# MOTOR.net
KiCad netlist of a schematic drawn in EAGLE
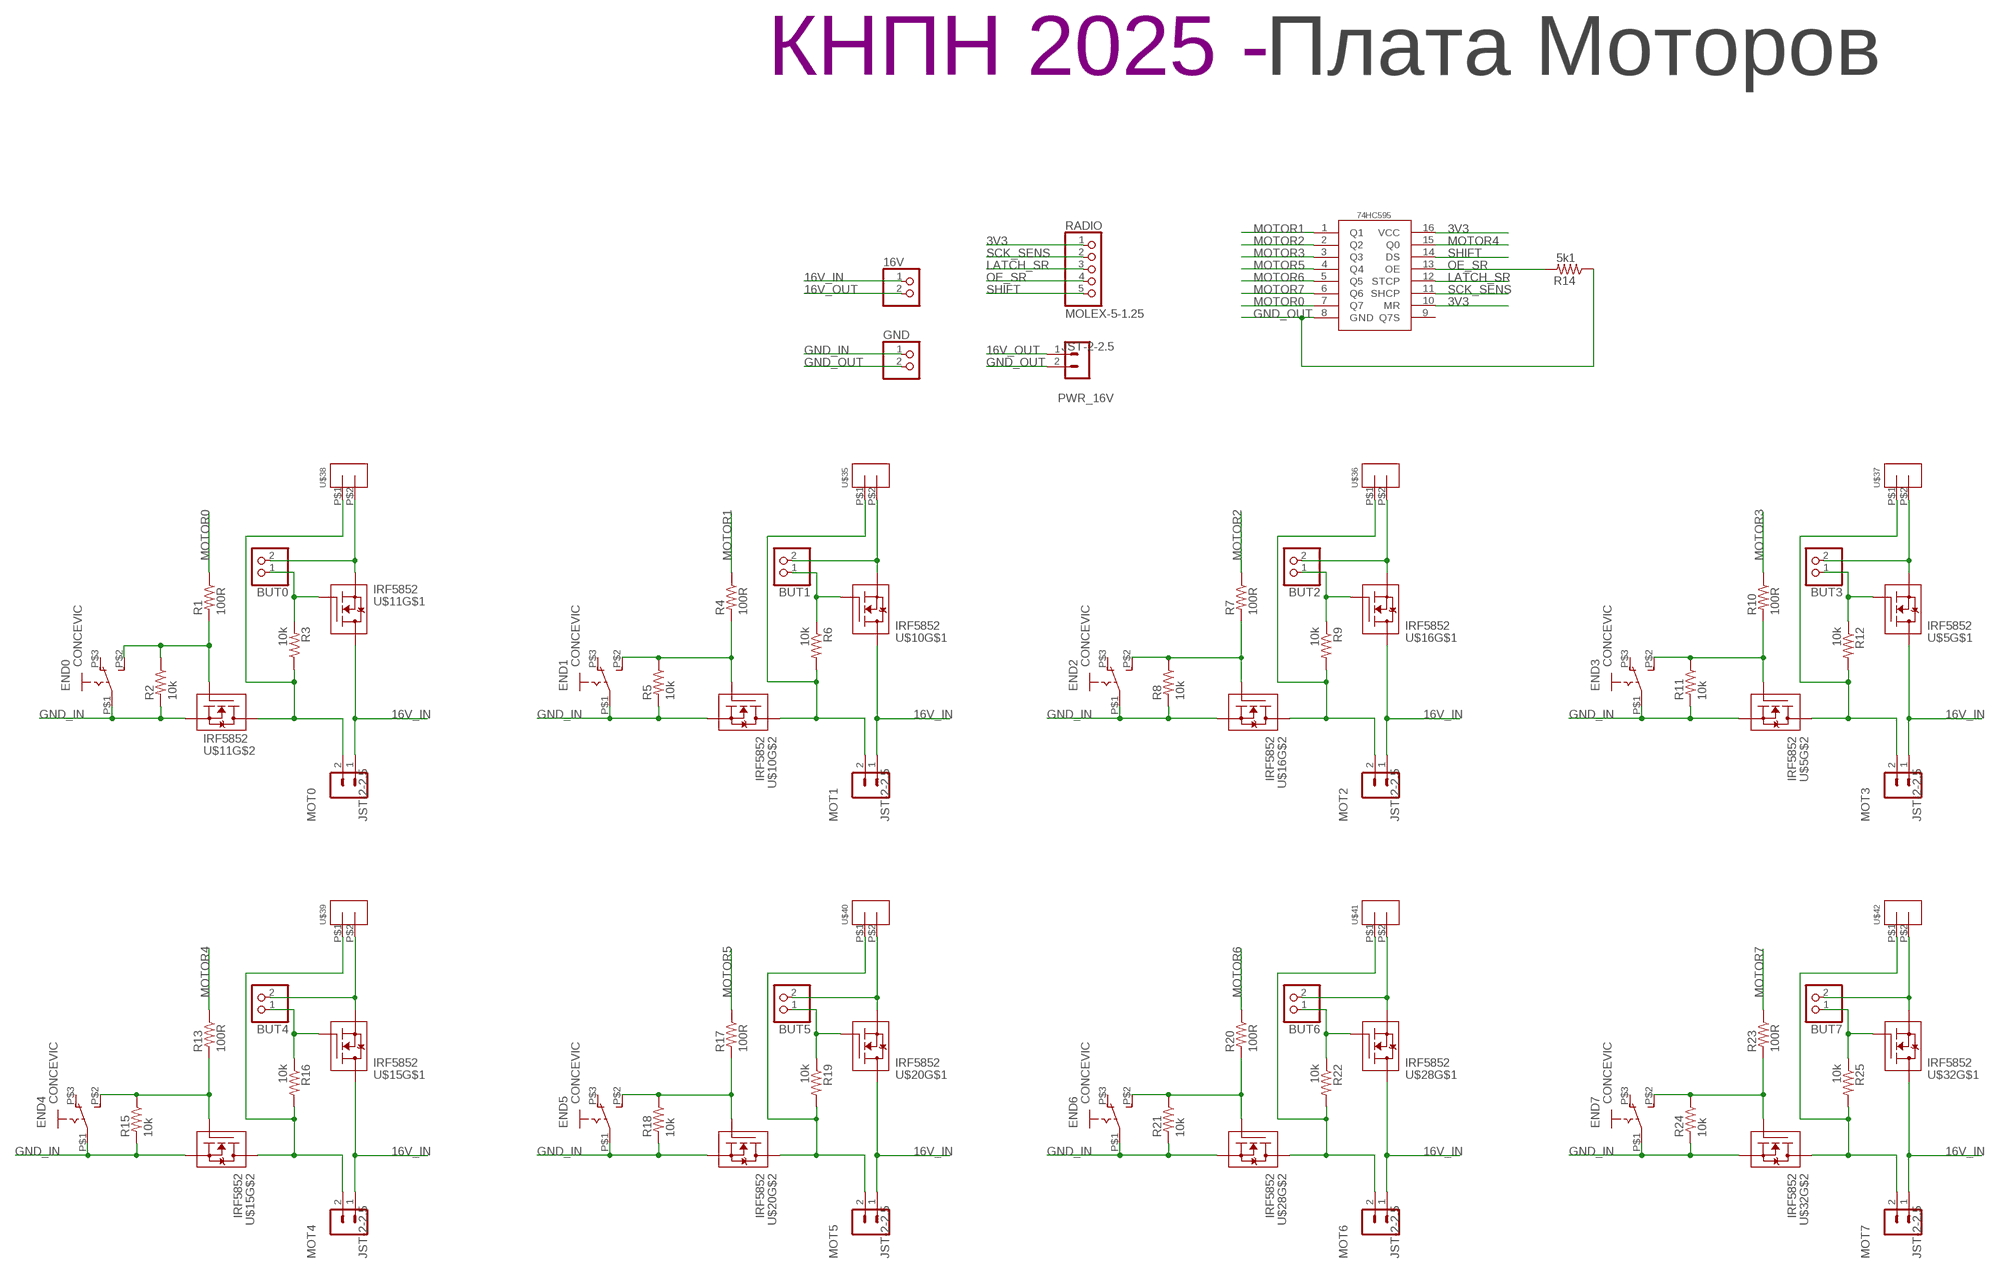
[diagram p0: schematic, sheet 1]

(export (version "E")
  (design (tool "Eeschema 10.0.6"))
  (components
    (comp (ref "16V")
      (value "PINHD-1X2/90")
      (footprint "eagle-import:1X02_90")
      (libsource (lib "eagle-import") (part "PINHD-1X2/90"))
    )
    (comp (ref "74HC595")
      (value "74HC595")
      (footprint "eagle-import:TSSOP16")
      (libsource (lib "eagle-import") (part "74HC595"))
    )
    (comp (ref "BUT0")
      (value "PINHD-1X2")
      (footprint "eagle-import:1X02")
      (libsource (lib "eagle-import") (part "PINHD-1X2"))
    )
    (comp (ref "BUT1")
      (value "PINHD-1X2")
      (footprint "eagle-import:1X02")
      (libsource (lib "eagle-import") (part "PINHD-1X2"))
    )
    (comp (ref "BUT2")
      (value "PINHD-1X2")
      (footprint "eagle-import:1X02")
      (libsource (lib "eagle-import") (part "PINHD-1X2"))
    )
    (comp (ref "BUT3")
      (value "PINHD-1X2")
      (footprint "eagle-import:1X02")
      (libsource (lib "eagle-import") (part "PINHD-1X2"))
    )
    (comp (ref "BUT4")
      (value "PINHD-1X2")
      (footprint "eagle-import:1X02")
      (libsource (lib "eagle-import") (part "PINHD-1X2"))
    )
    (comp (ref "BUT5")
      (value "PINHD-1X2")
      (footprint "eagle-import:1X02")
      (libsource (lib "eagle-import") (part "PINHD-1X2"))
    )
    (comp (ref "BUT6")
      (value "PINHD-1X2")
      (footprint "eagle-import:1X02")
      (libsource (lib "eagle-import") (part "PINHD-1X2"))
    )
    (comp (ref "BUT7")
      (value "PINHD-1X2")
      (footprint "eagle-import:1X02")
      (libsource (lib "eagle-import") (part "PINHD-1X2"))
    )
    (comp (ref "END0")
      (value "CONCEVIC")
      (footprint "eagle-import:CONCEVIC")
      (libsource (lib "eagle-import") (part "CONCEVIC"))
    )
    (comp (ref "END1")
      (value "CONCEVIC")
      (footprint "eagle-import:CONCEVIC")
      (libsource (lib "eagle-import") (part "CONCEVIC"))
    )
    (comp (ref "END2")
      (value "CONCEVIC")
      (footprint "eagle-import:CONCEVIC")
      (libsource (lib "eagle-import") (part "CONCEVIC"))
    )
    (comp (ref "END3")
      (value "CONCEVIC")
      (footprint "eagle-import:CONCEVIC")
      (libsource (lib "eagle-import") (part "CONCEVIC"))
    )
    (comp (ref "END4")
      (value "CONCEVIC")
      (footprint "eagle-import:CONCEVIC")
      (libsource (lib "eagle-import") (part "CONCEVIC"))
    )
    (comp (ref "END5")
      (value "CONCEVIC")
      (footprint "eagle-import:CONCEVIC")
      (libsource (lib "eagle-import") (part "CONCEVIC"))
    )
    (comp (ref "END6")
      (value "CONCEVIC")
      (footprint "eagle-import:CONCEVIC")
      (libsource (lib "eagle-import") (part "CONCEVIC"))
    )
    (comp (ref "END7")
      (value "CONCEVIC")
      (footprint "eagle-import:CONCEVIC")
      (libsource (lib "eagle-import") (part "CONCEVIC"))
    )
    (comp (ref "GND")
      (value "PINHD-1X2/90")
      (footprint "eagle-import:1X02_90")
      (libsource (lib "eagle-import") (part "PINHD-1X2/90"))
    )
    (comp (ref "MOT0")
      (value "JST-2-2.5")
      (footprint "eagle-import:JST-2-2.5")
      (libsource (lib "eagle-import") (part "JST-2-2.5"))
    )
    (comp (ref "MOT1")
      (value "JST-2-2.5")
      (footprint "eagle-import:JST-2-2.5")
      (libsource (lib "eagle-import") (part "JST-2-2.5"))
    )
    (comp (ref "MOT2")
      (value "JST-2-2.5")
      (footprint "eagle-import:JST-2-2.5")
      (libsource (lib "eagle-import") (part "JST-2-2.5"))
    )
    (comp (ref "MOT3")
      (value "JST-2-2.5")
      (footprint "eagle-import:JST-2-2.5")
      (libsource (lib "eagle-import") (part "JST-2-2.5"))
    )
    (comp (ref "MOT4")
      (value "JST-2-2.5")
      (footprint "eagle-import:JST-2-2.5")
      (libsource (lib "eagle-import") (part "JST-2-2.5"))
    )
    (comp (ref "MOT5")
      (value "JST-2-2.5")
      (footprint "eagle-import:JST-2-2.5")
      (libsource (lib "eagle-import") (part "JST-2-2.5"))
    )
    (comp (ref "MOT6")
      (value "JST-2-2.5")
      (footprint "eagle-import:JST-2-2.5")
      (libsource (lib "eagle-import") (part "JST-2-2.5"))
    )
    (comp (ref "MOT7")
      (value "JST-2-2.5")
      (footprint "eagle-import:JST-2-2.5")
      (libsource (lib "eagle-import") (part "JST-2-2.5"))
    )
    (comp (ref "PWR_16V")
      (value "JST-2-2.5")
      (footprint "eagle-import:JST-2-2.5")
      (libsource (lib "eagle-import") (part "JST-2-2.5"))
    )
    (comp (ref "R1")
      (value "100R")
      (footprint "eagle-import:R0603")
      (libsource (lib "eagle-import") (part "R-US_R0603"))
    )
    (comp (ref "R2")
      (value "10k")
      (footprint "eagle-import:R0603")
      (libsource (lib "eagle-import") (part "R-US_R0603"))
    )
    (comp (ref "R3")
      (value "10k")
      (footprint "eagle-import:R0603")
      (libsource (lib "eagle-import") (part "R-US_R0603"))
    )
    (comp (ref "R4")
      (value "100R")
      (footprint "eagle-import:R0603")
      (libsource (lib "eagle-import") (part "R-US_R0603"))
    )
    (comp (ref "R5")
      (value "10k")
      (footprint "eagle-import:R0603")
      (libsource (lib "eagle-import") (part "R-US_R0603"))
    )
    (comp (ref "R6")
      (value "10k")
      (footprint "eagle-import:R0603")
      (libsource (lib "eagle-import") (part "R-US_R0603"))
    )
    (comp (ref "R7")
      (value "100R")
      (footprint "eagle-import:R0603")
      (libsource (lib "eagle-import") (part "R-US_R0603"))
    )
    (comp (ref "R8")
      (value "10k")
      (footprint "eagle-import:R0603")
      (libsource (lib "eagle-import") (part "R-US_R0603"))
    )
    (comp (ref "R9")
      (value "10k")
      (footprint "eagle-import:R0603")
      (libsource (lib "eagle-import") (part "R-US_R0603"))
    )
    (comp (ref "R10")
      (value "100R")
      (footprint "eagle-import:R0603")
      (libsource (lib "eagle-import") (part "R-US_R0603"))
    )
    (comp (ref "R11")
      (value "10k")
      (footprint "eagle-import:R0603")
      (libsource (lib "eagle-import") (part "R-US_R0603"))
    )
    (comp (ref "R12")
      (value "10k")
      (footprint "eagle-import:R0603")
      (libsource (lib "eagle-import") (part "R-US_R0603"))
    )
    (comp (ref "R13")
      (value "100R")
      (footprint "eagle-import:R0603")
      (libsource (lib "eagle-import") (part "R-US_R0603"))
    )
    (comp (ref "R14")
      (value "5k1")
      (footprint "eagle-import:R0603")
      (libsource (lib "eagle-import") (part "R-US_R0603"))
    )
    (comp (ref "R15")
      (value "10k")
      (footprint "eagle-import:R0603")
      (libsource (lib "eagle-import") (part "R-US_R0603"))
    )
    (comp (ref "R16")
      (value "10k")
      (footprint "eagle-import:R0603")
      (libsource (lib "eagle-import") (part "R-US_R0603"))
    )
    (comp (ref "R17")
      (value "100R")
      (footprint "eagle-import:R0603")
      (libsource (lib "eagle-import") (part "R-US_R0603"))
    )
    (comp (ref "R18")
      (value "10k")
      (footprint "eagle-import:R0603")
      (libsource (lib "eagle-import") (part "R-US_R0603"))
    )
    (comp (ref "R19")
      (value "10k")
      (footprint "eagle-import:R0603")
      (libsource (lib "eagle-import") (part "R-US_R0603"))
    )
    (comp (ref "R20")
      (value "100R")
      (footprint "eagle-import:R0603")
      (libsource (lib "eagle-import") (part "R-US_R0603"))
    )
    (comp (ref "R21")
      (value "10k")
      (footprint "eagle-import:R0603")
      (libsource (lib "eagle-import") (part "R-US_R0603"))
    )
    (comp (ref "R22")
      (value "10k")
      (footprint "eagle-import:R0603")
      (libsource (lib "eagle-import") (part "R-US_R0603"))
    )
    (comp (ref "R23")
      (value "100R")
      (footprint "eagle-import:R0603")
      (libsource (lib "eagle-import") (part "R-US_R0603"))
    )
    (comp (ref "R24")
      (value "10k")
      (footprint "eagle-import:R0603")
      (libsource (lib "eagle-import") (part "R-US_R0603"))
    )
    (comp (ref "R25")
      (value "10k")
      (footprint "eagle-import:R0603")
      (libsource (lib "eagle-import") (part "R-US_R0603"))
    )
    (comp (ref "RADIO")
      (value "MOLEX-5-1.25")
      (footprint "eagle-import:53047-05")
      (libsource (lib "eagle-import") (part "MOLEX-5-1.25"))
    )
    (comp (ref "U$5")
      (value "IRF5852")
      (footprint "eagle-import:TSOP-6")
      (libsource (lib "eagle-import") (part "IRF5852"))
    )
    (comp (ref "U$9")
      (value "Плата Моторов")
      (footprint "eagle-import:LOGO")
      (libsource (lib "eagle-import") (part "LOGOPCB-{dblquote}{dblquote}"))
    )
    (comp (ref "U$10")
      (value "IRF5852")
      (footprint "eagle-import:TSOP-6")
      (libsource (lib "eagle-import") (part "IRF5852"))
    )
    (comp (ref "U$11")
      (value "IRF5852")
      (footprint "eagle-import:TSOP-6")
      (libsource (lib "eagle-import") (part "IRF5852"))
    )
    (comp (ref "U$15")
      (value "IRF5852")
      (footprint "eagle-import:TSOP-6")
      (libsource (lib "eagle-import") (part "IRF5852"))
    )
    (comp (ref "U$16")
      (value "IRF5852")
      (footprint "eagle-import:TSOP-6")
      (libsource (lib "eagle-import") (part "IRF5852"))
    )
    (comp (ref "U$20")
      (value "IRF5852")
      (footprint "eagle-import:TSOP-6")
      (libsource (lib "eagle-import") (part "IRF5852"))
    )
    (comp (ref "U$28")
      (value "IRF5852")
      (footprint "eagle-import:TSOP-6")
      (libsource (lib "eagle-import") (part "IRF5852"))
    )
    (comp (ref "U$32")
      (value "IRF5852")
      (footprint "eagle-import:TSOP-6")
      (libsource (lib "eagle-import") (part "IRF5852"))
    )
    (comp (ref "U$35")
      (value "CONTACT_SIDE_4MM_2PIN")
      (footprint "eagle-import:CONTACT_SIDE_4MM_2PIN")
      (libsource (lib "eagle-import") (part "CONTACT_SIDE_4MM_2PIN"))
    )
    (comp (ref "U$36")
      (value "CONTACT_SIDE_4MM_2PIN")
      (footprint "eagle-import:CONTACT_SIDE_4MM_2PIN")
      (libsource (lib "eagle-import") (part "CONTACT_SIDE_4MM_2PIN"))
    )
    (comp (ref "U$37")
      (value "CONTACT_SIDE_4MM_2PIN")
      (footprint "eagle-import:CONTACT_SIDE_4MM_2PIN")
      (libsource (lib "eagle-import") (part "CONTACT_SIDE_4MM_2PIN"))
    )
    (comp (ref "U$38")
      (value "CONTACT_SIDE_4MM_2PIN")
      (footprint "eagle-import:CONTACT_SIDE_4MM_2PIN")
      (libsource (lib "eagle-import") (part "CONTACT_SIDE_4MM_2PIN"))
    )
    (comp (ref "U$39")
      (value "CONTACT_SIDE_4MM_2PIN")
      (footprint "eagle-import:CONTACT_SIDE_4MM_2PIN")
      (libsource (lib "eagle-import") (part "CONTACT_SIDE_4MM_2PIN"))
    )
    (comp (ref "U$40")
      (value "CONTACT_SIDE_4MM_2PIN")
      (footprint "eagle-import:CONTACT_SIDE_4MM_2PIN")
      (libsource (lib "eagle-import") (part "CONTACT_SIDE_4MM_2PIN"))
    )
    (comp (ref "U$41")
      (value "CONTACT_SIDE_4MM_2PIN")
      (footprint "eagle-import:CONTACT_SIDE_4MM_2PIN")
      (libsource (lib "eagle-import") (part "CONTACT_SIDE_4MM_2PIN"))
    )
    (comp (ref "U$42")
      (value "CONTACT_SIDE_4MM_2PIN")
      (footprint "eagle-import:CONTACT_SIDE_4MM_2PIN")
      (libsource (lib "eagle-import") (part "CONTACT_SIDE_4MM_2PIN"))
    )
  )
  (nets
    (net (code "1") (name "/3V3") (class "Default")
      (node (ref "74HC595") (pin "10") (pinfunction "MR_10") (pintype "bidirectional"))
      (node (ref "74HC595") (pin "16") (pinfunction "VCC_16") (pintype "bidirectional"))
      (node (ref "RADIO") (pin "1") (pinfunction "1_1") (pintype "passive"))
    )
    (net (code "2") (name "/16V_IN") (class "Default")
      (node (ref "16V") (pin "1") (pinfunction "1_1") (pintype "passive"))
      (node (ref "MOT0") (pin "1") (pinfunction "1_1") (pintype "passive"))
      (node (ref "MOT1") (pin "1") (pinfunction "1_1") (pintype "passive"))
      (node (ref "MOT2") (pin "1") (pinfunction "1_1") (pintype "passive"))
      (node (ref "MOT3") (pin "1") (pinfunction "1_1") (pintype "passive"))
      (node (ref "MOT4") (pin "1") (pinfunction "1_1") (pintype "passive"))
      (node (ref "MOT5") (pin "1") (pinfunction "1_1") (pintype "passive"))
      (node (ref "MOT6") (pin "1") (pinfunction "1_1") (pintype "passive"))
      (node (ref "MOT7") (pin "1") (pinfunction "1_1") (pintype "passive"))
      (node (ref "U$10") (pin "P$6") (pinfunction "D1_P$6") (pintype "passive"))
      (node (ref "U$11") (pin "P$6") (pinfunction "D1_P$6") (pintype "passive"))
      (node (ref "U$15") (pin "P$6") (pinfunction "D1_P$6") (pintype "passive"))
      (node (ref "U$16") (pin "P$6") (pinfunction "D1_P$6") (pintype "passive"))
      (node (ref "U$20") (pin "P$6") (pinfunction "D1_P$6") (pintype "passive"))
      (node (ref "U$28") (pin "P$6") (pinfunction "D1_P$6") (pintype "passive"))
      (node (ref "U$32") (pin "P$6") (pinfunction "D1_P$6") (pintype "passive"))
      (node (ref "U$5") (pin "P$6") (pinfunction "D1_P$6") (pintype "passive"))
    )
    (net (code "3") (name "/16V_OUT") (class "Default")
      (node (ref "16V") (pin "2") (pinfunction "2_2") (pintype "passive"))
      (node (ref "PWR_16V") (pin "1") (pinfunction "1_1") (pintype "passive"))
    )
    (net (code "4") (name "/GND_IN") (class "Default")
      (node (ref "END0") (pin "P$1") (pinfunction "P_P$1") (pintype "passive"))
      (node (ref "END1") (pin "P$1") (pinfunction "P_P$1") (pintype "passive"))
      (node (ref "END2") (pin "P$1") (pinfunction "P_P$1") (pintype "passive"))
      (node (ref "END3") (pin "P$1") (pinfunction "P_P$1") (pintype "passive"))
      (node (ref "END4") (pin "P$1") (pinfunction "P_P$1") (pintype "passive"))
      (node (ref "END5") (pin "P$1") (pinfunction "P_P$1") (pintype "passive"))
      (node (ref "END6") (pin "P$1") (pinfunction "P_P$1") (pintype "passive"))
      (node (ref "END7") (pin "P$1") (pinfunction "P_P$1") (pintype "passive"))
      (node (ref "GND") (pin "1") (pinfunction "1_1") (pintype "passive"))
      (node (ref "R11") (pin "2") (pinfunction "2_2") (pintype "passive"))
      (node (ref "R15") (pin "2") (pinfunction "2_2") (pintype "passive"))
      (node (ref "R18") (pin "2") (pinfunction "2_2") (pintype "passive"))
      (node (ref "R2") (pin "2") (pinfunction "2_2") (pintype "passive"))
      (node (ref "R21") (pin "2") (pinfunction "2_2") (pintype "passive"))
      (node (ref "R24") (pin "2") (pinfunction "2_2") (pintype "passive"))
      (node (ref "R5") (pin "2") (pinfunction "2_2") (pintype "passive"))
      (node (ref "R8") (pin "2") (pinfunction "2_2") (pintype "passive"))
      (node (ref "U$10") (pin "P$2") (pinfunction "S1_P$2") (pintype "passive"))
      (node (ref "U$11") (pin "P$2") (pinfunction "S1_P$2") (pintype "passive"))
      (node (ref "U$15") (pin "P$2") (pinfunction "S1_P$2") (pintype "passive"))
      (node (ref "U$16") (pin "P$2") (pinfunction "S1_P$2") (pintype "passive"))
      (node (ref "U$20") (pin "P$2") (pinfunction "S1_P$2") (pintype "passive"))
      (node (ref "U$28") (pin "P$2") (pinfunction "S1_P$2") (pintype "passive"))
      (node (ref "U$32") (pin "P$2") (pinfunction "S1_P$2") (pintype "passive"))
      (node (ref "U$5") (pin "P$2") (pinfunction "S1_P$2") (pintype "passive"))
    )
    (net (code "5") (name "/GND_OUT") (class "Default")
      (node (ref "74HC595") (pin "8") (pinfunction "GND_8") (pintype "bidirectional"))
      (node (ref "GND") (pin "2") (pinfunction "2_2") (pintype "passive"))
      (node (ref "PWR_16V") (pin "2") (pinfunction "2_2") (pintype "passive"))
      (node (ref "R14") (pin "1") (pinfunction "1_1") (pintype "passive"))
    )
    (net (code "6") (name "/LATCH_SR") (class "Default")
      (node (ref "74HC595") (pin "12") (pinfunction "STCP_12") (pintype "bidirectional"))
      (node (ref "RADIO") (pin "3") (pinfunction "3_3") (pintype "passive"))
    )
    (net (code "7") (name "/MOTOR0") (class "Default")
      (node (ref "74HC595") (pin "7") (pinfunction "Q7_7") (pintype "bidirectional"))
      (node (ref "R1") (pin "1") (pinfunction "1_1") (pintype "passive"))
    )
    (net (code "8") (name "/MOTOR1") (class "Default")
      (node (ref "74HC595") (pin "1") (pinfunction "Q1_1") (pintype "bidirectional"))
      (node (ref "R4") (pin "1") (pinfunction "1_1") (pintype "passive"))
    )
    (net (code "9") (name "/MOTOR2") (class "Default")
      (node (ref "74HC595") (pin "2") (pinfunction "Q2_2") (pintype "bidirectional"))
      (node (ref "R7") (pin "1") (pinfunction "1_1") (pintype "passive"))
    )
    (net (code "10") (name "/MOTOR3") (class "Default")
      (node (ref "74HC595") (pin "3") (pinfunction "Q3_3") (pintype "bidirectional"))
      (node (ref "R10") (pin "1") (pinfunction "1_1") (pintype "passive"))
    )
    (net (code "11") (name "/MOTOR4") (class "Default")
      (node (ref "74HC595") (pin "15") (pinfunction "Q0_15") (pintype "bidirectional"))
      (node (ref "R13") (pin "1") (pinfunction "1_1") (pintype "passive"))
    )
    (net (code "12") (name "/MOTOR5") (class "Default")
      (node (ref "74HC595") (pin "4") (pinfunction "Q4_4") (pintype "bidirectional"))
      (node (ref "R17") (pin "1") (pinfunction "1_1") (pintype "passive"))
    )
    (net (code "13") (name "/MOTOR6") (class "Default")
      (node (ref "74HC595") (pin "5") (pinfunction "Q5_5") (pintype "bidirectional"))
      (node (ref "R20") (pin "1") (pinfunction "1_1") (pintype "passive"))
    )
    (net (code "14") (name "/MOTOR7") (class "Default")
      (node (ref "74HC595") (pin "6") (pinfunction "Q6_6") (pintype "bidirectional"))
      (node (ref "R23") (pin "1") (pinfunction "1_1") (pintype "passive"))
    )
    (net (code "15") (name "/OE_SR") (class "Default")
      (node (ref "74HC595") (pin "13") (pinfunction "OE_13") (pintype "bidirectional"))
      (node (ref "R14") (pin "2") (pinfunction "2_2") (pintype "passive"))
      (node (ref "RADIO") (pin "4") (pinfunction "4_4") (pintype "passive"))
    )
    (net (code "16") (name "/SCK_SENS") (class "Default")
      (node (ref "74HC595") (pin "11") (pinfunction "SHCP_11") (pintype "bidirectional"))
      (node (ref "RADIO") (pin "2") (pinfunction "2_2") (pintype "passive"))
    )
    (net (code "17") (name "/SHIFT") (class "Default")
      (node (ref "74HC595") (pin "14") (pinfunction "DS_14") (pintype "bidirectional"))
      (node (ref "RADIO") (pin "5") (pinfunction "5_5") (pintype "passive"))
    )
    (net (code "18") (name "Net-(END0-S)") (class "Default")
      (node (ref "END0") (pin "P$2") (pinfunction "S_P$2") (pintype "passive"))
      (node (ref "R1") (pin "2") (pinfunction "2_2") (pintype "passive"))
      (node (ref "R2") (pin "1") (pinfunction "1_1") (pintype "passive"))
      (node (ref "U$11") (pin "P$3") (pinfunction "G1_P$3") (pintype "passive"))
    )
    (net (code "19") (name "Net-(END1-S)") (class "Default")
      (node (ref "END1") (pin "P$2") (pinfunction "S_P$2") (pintype "passive"))
      (node (ref "R4") (pin "2") (pinfunction "2_2") (pintype "passive"))
      (node (ref "R5") (pin "1") (pinfunction "1_1") (pintype "passive"))
      (node (ref "U$10") (pin "P$3") (pinfunction "G1_P$3") (pintype "passive"))
    )
    (net (code "20") (name "Net-(END2-S)") (class "Default")
      (node (ref "END2") (pin "P$2") (pinfunction "S_P$2") (pintype "passive"))
      (node (ref "R7") (pin "2") (pinfunction "2_2") (pintype "passive"))
      (node (ref "R8") (pin "1") (pinfunction "1_1") (pintype "passive"))
      (node (ref "U$16") (pin "P$3") (pinfunction "G1_P$3") (pintype "passive"))
    )
    (net (code "21") (name "Net-(END3-S)") (class "Default")
      (node (ref "END3") (pin "P$2") (pinfunction "S_P$2") (pintype "passive"))
      (node (ref "R10") (pin "2") (pinfunction "2_2") (pintype "passive"))
      (node (ref "R11") (pin "1") (pinfunction "1_1") (pintype "passive"))
      (node (ref "U$5") (pin "P$3") (pinfunction "G1_P$3") (pintype "passive"))
    )
    (net (code "22") (name "Net-(END4-S)") (class "Default")
      (node (ref "END4") (pin "P$2") (pinfunction "S_P$2") (pintype "passive"))
      (node (ref "R13") (pin "2") (pinfunction "2_2") (pintype "passive"))
      (node (ref "R15") (pin "1") (pinfunction "1_1") (pintype "passive"))
      (node (ref "U$15") (pin "P$3") (pinfunction "G1_P$3") (pintype "passive"))
    )
    (net (code "23") (name "Net-(END5-S)") (class "Default")
      (node (ref "END5") (pin "P$2") (pinfunction "S_P$2") (pintype "passive"))
      (node (ref "R17") (pin "2") (pinfunction "2_2") (pintype "passive"))
      (node (ref "R18") (pin "1") (pinfunction "1_1") (pintype "passive"))
      (node (ref "U$20") (pin "P$3") (pinfunction "G1_P$3") (pintype "passive"))
    )
    (net (code "24") (name "Net-(END6-S)") (class "Default")
      (node (ref "END6") (pin "P$2") (pinfunction "S_P$2") (pintype "passive"))
      (node (ref "R20") (pin "2") (pinfunction "2_2") (pintype "passive"))
      (node (ref "R21") (pin "1") (pinfunction "1_1") (pintype "passive"))
      (node (ref "U$28") (pin "P$3") (pinfunction "G1_P$3") (pintype "passive"))
    )
    (net (code "25") (name "Net-(END7-S)") (class "Default")
      (node (ref "END7") (pin "P$2") (pinfunction "S_P$2") (pintype "passive"))
      (node (ref "R23") (pin "2") (pinfunction "2_2") (pintype "passive"))
      (node (ref "R24") (pin "1") (pinfunction "1_1") (pintype "passive"))
      (node (ref "U$32") (pin "P$3") (pinfunction "G1_P$3") (pintype "passive"))
    )
    (net (code "26") (name "Net-(U$5A-G1)") (class "Default")
      (node (ref "BUT3") (pin "1") (pinfunction "1_1") (pintype "passive"))
      (node (ref "R12") (pin "1") (pinfunction "1_1") (pintype "passive"))
      (node (ref "U$5") (pin "P$1") (pinfunction "G1_P$1") (pintype "passive"))
    )
    (net (code "27") (name "Net-(U$5A-S1)") (class "Default")
      (node (ref "BUT3") (pin "2") (pinfunction "2_2") (pintype "passive"))
      (node (ref "U$37") (pin "P$2") (pinfunction "P$2_P$2") (pintype "bidirectional"))
      (node (ref "U$5") (pin "P$5") (pinfunction "S1_P$5") (pintype "passive"))
    )
    (net (code "28") (name "Net-(U$5B-D1)") (class "Default")
      (node (ref "MOT3") (pin "2") (pinfunction "2_2") (pintype "passive"))
      (node (ref "R12") (pin "2") (pinfunction "2_2") (pintype "passive"))
      (node (ref "U$37") (pin "P$1") (pinfunction "P$1_P$1") (pintype "bidirectional"))
      (node (ref "U$5") (pin "P$4") (pinfunction "D1_P$4") (pintype "passive"))
    )
    (net (code "29") (name "Net-(U$10A-G1)") (class "Default")
      (node (ref "BUT1") (pin "1") (pinfunction "1_1") (pintype "passive"))
      (node (ref "R6") (pin "1") (pinfunction "1_1") (pintype "passive"))
      (node (ref "U$10") (pin "P$1") (pinfunction "G1_P$1") (pintype "passive"))
    )
    (net (code "30") (name "Net-(U$10A-S1)") (class "Default")
      (node (ref "BUT1") (pin "2") (pinfunction "2_2") (pintype "passive"))
      (node (ref "U$10") (pin "P$5") (pinfunction "S1_P$5") (pintype "passive"))
      (node (ref "U$35") (pin "P$2") (pinfunction "P$2_P$2") (pintype "bidirectional"))
    )
    (net (code "31") (name "Net-(U$10B-D1)") (class "Default")
      (node (ref "MOT1") (pin "2") (pinfunction "2_2") (pintype "passive"))
      (node (ref "R6") (pin "2") (pinfunction "2_2") (pintype "passive"))
      (node (ref "U$10") (pin "P$4") (pinfunction "D1_P$4") (pintype "passive"))
      (node (ref "U$35") (pin "P$1") (pinfunction "P$1_P$1") (pintype "bidirectional"))
    )
    (net (code "32") (name "Net-(U$11A-G1)") (class "Default")
      (node (ref "BUT0") (pin "1") (pinfunction "1_1") (pintype "passive"))
      (node (ref "R3") (pin "2") (pinfunction "2_2") (pintype "passive"))
      (node (ref "U$11") (pin "P$1") (pinfunction "G1_P$1") (pintype "passive"))
    )
    (net (code "33") (name "Net-(U$11A-S1)") (class "Default")
      (node (ref "BUT0") (pin "2") (pinfunction "2_2") (pintype "passive"))
      (node (ref "U$11") (pin "P$5") (pinfunction "S1_P$5") (pintype "passive"))
      (node (ref "U$38") (pin "P$2") (pinfunction "P$2_P$2") (pintype "bidirectional"))
    )
    (net (code "34") (name "Net-(U$11B-D1)") (class "Default")
      (node (ref "MOT0") (pin "2") (pinfunction "2_2") (pintype "passive"))
      (node (ref "R3") (pin "1") (pinfunction "1_1") (pintype "passive"))
      (node (ref "U$11") (pin "P$4") (pinfunction "D1_P$4") (pintype "passive"))
      (node (ref "U$38") (pin "P$1") (pinfunction "P$1_P$1") (pintype "bidirectional"))
    )
    (net (code "35") (name "Net-(U$15A-G1)") (class "Default")
      (node (ref "BUT4") (pin "1") (pinfunction "1_1") (pintype "passive"))
      (node (ref "R16") (pin "1") (pinfunction "1_1") (pintype "passive"))
      (node (ref "U$15") (pin "P$1") (pinfunction "G1_P$1") (pintype "passive"))
    )
    (net (code "36") (name "Net-(U$15A-S1)") (class "Default")
      (node (ref "BUT4") (pin "2") (pinfunction "2_2") (pintype "passive"))
      (node (ref "U$15") (pin "P$5") (pinfunction "S1_P$5") (pintype "passive"))
      (node (ref "U$39") (pin "P$2") (pinfunction "P$2_P$2") (pintype "bidirectional"))
    )
    (net (code "37") (name "Net-(U$15B-D1)") (class "Default")
      (node (ref "MOT4") (pin "2") (pinfunction "2_2") (pintype "passive"))
      (node (ref "R16") (pin "2") (pinfunction "2_2") (pintype "passive"))
      (node (ref "U$15") (pin "P$4") (pinfunction "D1_P$4") (pintype "passive"))
      (node (ref "U$39") (pin "P$1") (pinfunction "P$1_P$1") (pintype "bidirectional"))
    )
    (net (code "38") (name "Net-(U$16A-G1)") (class "Default")
      (node (ref "BUT2") (pin "1") (pinfunction "1_1") (pintype "passive"))
      (node (ref "R9") (pin "1") (pinfunction "1_1") (pintype "passive"))
      (node (ref "U$16") (pin "P$1") (pinfunction "G1_P$1") (pintype "passive"))
    )
    (net (code "39") (name "Net-(U$16A-S1)") (class "Default")
      (node (ref "BUT2") (pin "2") (pinfunction "2_2") (pintype "passive"))
      (node (ref "U$16") (pin "P$5") (pinfunction "S1_P$5") (pintype "passive"))
      (node (ref "U$36") (pin "P$2") (pinfunction "P$2_P$2") (pintype "bidirectional"))
    )
    (net (code "40") (name "Net-(U$16B-D1)") (class "Default")
      (node (ref "MOT2") (pin "2") (pinfunction "2_2") (pintype "passive"))
      (node (ref "R9") (pin "2") (pinfunction "2_2") (pintype "passive"))
      (node (ref "U$16") (pin "P$4") (pinfunction "D1_P$4") (pintype "passive"))
      (node (ref "U$36") (pin "P$1") (pinfunction "P$1_P$1") (pintype "bidirectional"))
    )
    (net (code "41") (name "Net-(U$20A-G1)") (class "Default")
      (node (ref "BUT5") (pin "1") (pinfunction "1_1") (pintype "passive"))
      (node (ref "R19") (pin "1") (pinfunction "1_1") (pintype "passive"))
      (node (ref "U$20") (pin "P$1") (pinfunction "G1_P$1") (pintype "passive"))
    )
    (net (code "42") (name "Net-(U$20A-S1)") (class "Default")
      (node (ref "BUT5") (pin "2") (pinfunction "2_2") (pintype "passive"))
      (node (ref "U$20") (pin "P$5") (pinfunction "S1_P$5") (pintype "passive"))
      (node (ref "U$40") (pin "P$2") (pinfunction "P$2_P$2") (pintype "bidirectional"))
    )
    (net (code "43") (name "Net-(U$20B-D1)") (class "Default")
      (node (ref "MOT5") (pin "2") (pinfunction "2_2") (pintype "passive"))
      (node (ref "R19") (pin "2") (pinfunction "2_2") (pintype "passive"))
      (node (ref "U$20") (pin "P$4") (pinfunction "D1_P$4") (pintype "passive"))
      (node (ref "U$40") (pin "P$1") (pinfunction "P$1_P$1") (pintype "bidirectional"))
    )
    (net (code "44") (name "Net-(U$28A-G1)") (class "Default")
      (node (ref "BUT6") (pin "1") (pinfunction "1_1") (pintype "passive"))
      (node (ref "R22") (pin "1") (pinfunction "1_1") (pintype "passive"))
      (node (ref "U$28") (pin "P$1") (pinfunction "G1_P$1") (pintype "passive"))
    )
    (net (code "45") (name "Net-(U$28A-S1)") (class "Default")
      (node (ref "BUT6") (pin "2") (pinfunction "2_2") (pintype "passive"))
      (node (ref "U$28") (pin "P$5") (pinfunction "S1_P$5") (pintype "passive"))
      (node (ref "U$41") (pin "P$2") (pinfunction "P$2_P$2") (pintype "bidirectional"))
    )
    (net (code "46") (name "Net-(U$28B-D1)") (class "Default")
      (node (ref "MOT6") (pin "2") (pinfunction "2_2") (pintype "passive"))
      (node (ref "R22") (pin "2") (pinfunction "2_2") (pintype "passive"))
      (node (ref "U$28") (pin "P$4") (pinfunction "D1_P$4") (pintype "passive"))
      (node (ref "U$41") (pin "P$1") (pinfunction "P$1_P$1") (pintype "bidirectional"))
    )
    (net (code "47") (name "Net-(U$32A-G1)") (class "Default")
      (node (ref "BUT7") (pin "1") (pinfunction "1_1") (pintype "passive"))
      (node (ref "R25") (pin "1") (pinfunction "1_1") (pintype "passive"))
      (node (ref "U$32") (pin "P$1") (pinfunction "G1_P$1") (pintype "passive"))
    )
    (net (code "48") (name "Net-(U$32A-S1)") (class "Default")
      (node (ref "BUT7") (pin "2") (pinfunction "2_2") (pintype "passive"))
      (node (ref "U$32") (pin "P$5") (pinfunction "S1_P$5") (pintype "passive"))
      (node (ref "U$42") (pin "P$2") (pinfunction "P$2_P$2") (pintype "bidirectional"))
    )
    (net (code "49") (name "Net-(U$32B-D1)") (class "Default")
      (node (ref "MOT7") (pin "2") (pinfunction "2_2") (pintype "passive"))
      (node (ref "R25") (pin "2") (pinfunction "2_2") (pintype "passive"))
      (node (ref "U$32") (pin "P$4") (pinfunction "D1_P$4") (pintype "passive"))
      (node (ref "U$42") (pin "P$1") (pinfunction "P$1_P$1") (pintype "bidirectional"))
    )
    (net (code "50") (name "unconnected-(74HC595-Q7S-Pad9)") (class "Default")
      (node (ref "74HC595") (pin "9") (pinfunction "Q7S_9") (pintype "bidirectional"))
    )
    (net (code "51") (name "unconnected-(END0-O-PadP$3)") (class "Default")
      (node (ref "END0") (pin "P$3") (pinfunction "O_P$3") (pintype "passive"))
    )
    (net (code "52") (name "unconnected-(END1-O-PadP$3)") (class "Default")
      (node (ref "END1") (pin "P$3") (pinfunction "O_P$3") (pintype "passive"))
    )
    (net (code "53") (name "unconnected-(END2-O-PadP$3)") (class "Default")
      (node (ref "END2") (pin "P$3") (pinfunction "O_P$3") (pintype "passive"))
    )
    (net (code "54") (name "unconnected-(END3-O-PadP$3)") (class "Default")
      (node (ref "END3") (pin "P$3") (pinfunction "O_P$3") (pintype "passive"))
    )
    (net (code "55") (name "unconnected-(END4-O-PadP$3)") (class "Default")
      (node (ref "END4") (pin "P$3") (pinfunction "O_P$3") (pintype "passive"))
    )
    (net (code "56") (name "unconnected-(END5-O-PadP$3)") (class "Default")
      (node (ref "END5") (pin "P$3") (pinfunction "O_P$3") (pintype "passive"))
    )
    (net (code "57") (name "unconnected-(END6-O-PadP$3)") (class "Default")
      (node (ref "END6") (pin "P$3") (pinfunction "O_P$3") (pintype "passive"))
    )
    (net (code "58") (name "unconnected-(END7-O-PadP$3)") (class "Default")
      (node (ref "END7") (pin "P$3") (pinfunction "O_P$3") (pintype "passive"))
    )
  )
)
